# Murray.net
KiCad netlist of a schematic drawn in EAGLE
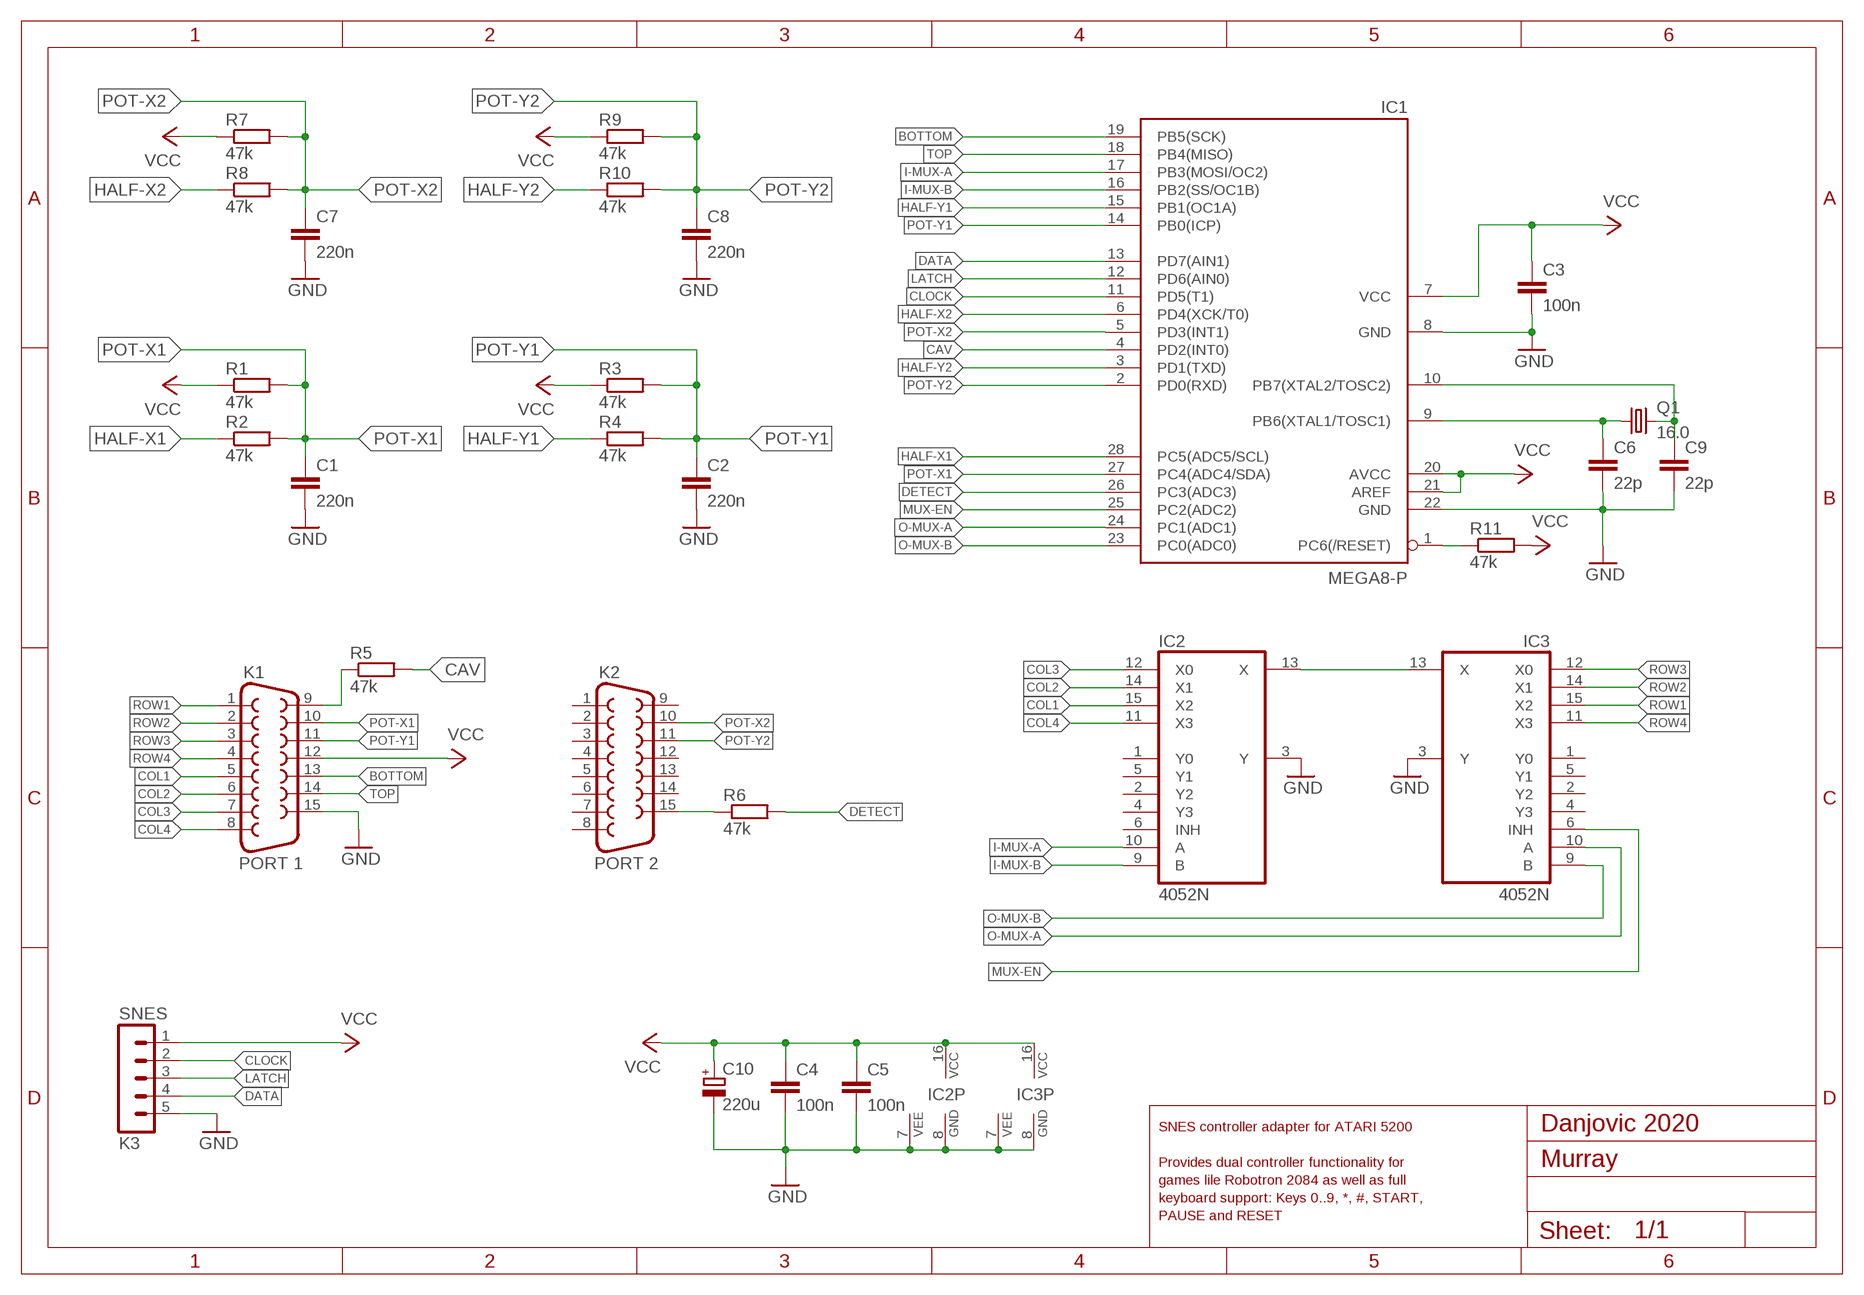
[diagram p0: schematic, sheet 1]

(export (version "E")
  (design (tool "Eeschema 10.0.6"))
  (components
    (comp (ref "C1")
      (value "220n")
      (footprint "eagle-import:C050-030X075")
      (libsource (lib "eagle-import") (part "C-EU050-030X075"))
    )
    (comp (ref "C2")
      (value "220n")
      (footprint "eagle-import:C050-030X075")
      (libsource (lib "eagle-import") (part "C-EU050-030X075"))
    )
    (comp (ref "C3")
      (value "100n")
      (footprint "eagle-import:C050-024X044")
      (libsource (lib "eagle-import") (part "C-EU050-024X044"))
    )
    (comp (ref "C4")
      (value "100n")
      (footprint "eagle-import:C050-024X044")
      (libsource (lib "eagle-import") (part "C-EU050-024X044"))
    )
    (comp (ref "C5")
      (value "100n")
      (footprint "eagle-import:C050-024X044")
      (libsource (lib "eagle-import") (part "C-EU050-024X044"))
    )
    (comp (ref "C6")
      (value "22p")
      (footprint "eagle-import:C025-024X044")
      (libsource (lib "eagle-import") (part "C-EU025-024X044"))
    )
    (comp (ref "C7")
      (value "220n")
      (footprint "eagle-import:C050-030X075")
      (libsource (lib "eagle-import") (part "C-EU050-030X075"))
    )
    (comp (ref "C8")
      (value "220n")
      (footprint "eagle-import:C050-030X075")
      (libsource (lib "eagle-import") (part "C-EU050-030X075"))
    )
    (comp (ref "C9")
      (value "22p")
      (footprint "eagle-import:C025-024X044")
      (libsource (lib "eagle-import") (part "C-EU025-024X044"))
    )
    (comp (ref "C10")
      (value "220u")
      (footprint "eagle-import:E2,5-6E")
      (libsource (lib "eagle-import") (part "CPOL-EUE2,5-6E"))
    )
    (comp (ref "IC1")
      (value "MEGA8-P")
      (footprint "eagle-import:DIL28-3")
      (libsource (lib "eagle-import") (part "MEGA8-P"))
    )
    (comp (ref "IC2")
      (value "4052N")
      (footprint "eagle-import:DIL16")
      (libsource (lib "eagle-import") (part "4052N"))
    )
    (comp (ref "IC3")
      (value "4052N")
      (footprint "eagle-import:DIL16")
      (libsource (lib "eagle-import") (part "4052N"))
    )
    (comp (ref "K1")
      (value "PORT 1")
      (footprint "eagle-import:F15H")
      (libsource (lib "eagle-import") (part "F15H"))
    )
    (comp (ref "K2")
      (value "PORT 2")
      (footprint "eagle-import:F15H")
      (libsource (lib "eagle-import") (part "F15H"))
    )
    (comp (ref "K3")
      (value "SNES")
      (footprint "eagle-import:MA05-1")
      (libsource (lib "eagle-import") (part "MA05-1"))
    )
    (comp (ref "Q1")
      (value "16.0")
      (footprint "eagle-import:TC26V")
      (libsource (lib "eagle-import") (part "CRYSTALTC26V"))
    )
    (comp (ref "R1")
      (value "47k")
      (footprint "eagle-import:0204_7")
      (libsource (lib "eagle-import") (part "R-EU_0204/7"))
    )
    (comp (ref "R2")
      (value "47k")
      (footprint "eagle-import:0204_7")
      (libsource (lib "eagle-import") (part "R-EU_0204/7"))
    )
    (comp (ref "R3")
      (value "47k")
      (footprint "eagle-import:0204_7")
      (libsource (lib "eagle-import") (part "R-EU_0204/7"))
    )
    (comp (ref "R4")
      (value "47k")
      (footprint "eagle-import:0204_7")
      (libsource (lib "eagle-import") (part "R-EU_0204/7"))
    )
    (comp (ref "R5")
      (value "47k")
      (footprint "eagle-import:0204_7")
      (libsource (lib "eagle-import") (part "R-EU_0204/7"))
    )
    (comp (ref "R6")
      (value "47k")
      (footprint "eagle-import:0204_7")
      (libsource (lib "eagle-import") (part "R-EU_0204/7"))
    )
    (comp (ref "R7")
      (value "47k")
      (footprint "eagle-import:0204_7")
      (libsource (lib "eagle-import") (part "R-EU_0204/7"))
    )
    (comp (ref "R8")
      (value "47k")
      (footprint "eagle-import:0204_7")
      (libsource (lib "eagle-import") (part "R-EU_0204/7"))
    )
    (comp (ref "R9")
      (value "47k")
      (footprint "eagle-import:0204_7")
      (libsource (lib "eagle-import") (part "R-EU_0204/7"))
    )
    (comp (ref "R10")
      (value "47k")
      (footprint "eagle-import:0204_7")
      (libsource (lib "eagle-import") (part "R-EU_0204/7"))
    )
    (comp (ref "R11")
      (value "47k")
      (footprint "eagle-import:0204_7")
      (libsource (lib "eagle-import") (part "R-EU_0204/7"))
    )
  )
  (nets
    (net (code "1") (name "BOTTOM") (class "Default")
      (node (ref "IC1") (pin "19") (pinfunction "PB5(SCK)_19") (pintype "bidirectional"))
      (node (ref "K1") (pin "13") (pinfunction "13_13") (pintype "passive"))
    )
    (net (code "2") (name "CAV") (class "Default")
      (node (ref "IC1") (pin "4") (pinfunction "PD2(INT0)_4") (pintype "bidirectional"))
      (node (ref "R5") (pin "2") (pinfunction "2_2") (pintype "passive"))
    )
    (net (code "3") (name "CLOCK") (class "Default")
      (node (ref "IC1") (pin "11") (pinfunction "PD5(T1)_11") (pintype "bidirectional"))
      (node (ref "K3") (pin "2") (pinfunction "2_2") (pintype "passive"))
    )
    (net (code "4") (name "COL1") (class "Default")
      (node (ref "IC2") (pin "15") (pinfunction "X2_15") (pintype "bidirectional"))
      (node (ref "K1") (pin "5") (pinfunction "5_5") (pintype "passive"))
    )
    (net (code "5") (name "COL2") (class "Default")
      (node (ref "IC2") (pin "14") (pinfunction "X1_14") (pintype "bidirectional"))
      (node (ref "K1") (pin "6") (pinfunction "6_6") (pintype "passive"))
    )
    (net (code "6") (name "COL3") (class "Default")
      (node (ref "IC2") (pin "12") (pinfunction "X0_12") (pintype "bidirectional"))
      (node (ref "K1") (pin "7") (pinfunction "7_7") (pintype "passive"))
    )
    (net (code "7") (name "COL4") (class "Default")
      (node (ref "IC2") (pin "11") (pinfunction "X3_11") (pintype "bidirectional"))
      (node (ref "K1") (pin "8") (pinfunction "8_8") (pintype "passive"))
    )
    (net (code "8") (name "DATA") (class "Default")
      (node (ref "IC1") (pin "13") (pinfunction "PD7(AIN1)_13") (pintype "bidirectional"))
      (node (ref "K3") (pin "4") (pinfunction "4_4") (pintype "passive"))
    )
    (net (code "9") (name "DETECT") (class "Default")
      (node (ref "IC1") (pin "26") (pinfunction "PC3(ADC3)_26") (pintype "bidirectional"))
      (node (ref "R6") (pin "2") (pinfunction "2_2") (pintype "passive"))
    )
    (net (code "10") (name "GND") (class "Default")
      (node (ref "C1") (pin "2") (pinfunction "2_2") (pintype "passive"))
      (node (ref "C10") (pin "-") (pinfunction "-_-") (pintype "passive"))
      (node (ref "C2") (pin "2") (pinfunction "2_2") (pintype "passive"))
      (node (ref "C3") (pin "2") (pinfunction "2_2") (pintype "passive"))
      (node (ref "C4") (pin "2") (pinfunction "2_2") (pintype "passive"))
      (node (ref "C5") (pin "2") (pinfunction "2_2") (pintype "passive"))
      (node (ref "C6") (pin "2") (pinfunction "2_2") (pintype "passive"))
      (node (ref "C7") (pin "2") (pinfunction "2_2") (pintype "passive"))
      (node (ref "C8") (pin "2") (pinfunction "2_2") (pintype "passive"))
      (node (ref "C9") (pin "2") (pinfunction "2_2") (pintype "passive"))
      (node (ref "IC1") (pin "22") (pinfunction "GND_22") (pintype "power_in"))
      (node (ref "IC1") (pin "8") (pinfunction "GND_8") (pintype "power_in"))
      (node (ref "IC2") (pin "3") (pinfunction "Y_3") (pintype "bidirectional"))
      (node (ref "IC2") (pin "7") (pinfunction "VEE_7") (pintype "power_in"))
      (node (ref "IC2") (pin "8") (pinfunction "GND_8") (pintype "power_in"))
      (node (ref "IC3") (pin "3") (pinfunction "Y_3") (pintype "bidirectional"))
      (node (ref "IC3") (pin "7") (pinfunction "VEE_7") (pintype "power_in"))
      (node (ref "IC3") (pin "8") (pinfunction "GND_8") (pintype "power_in"))
      (node (ref "K1") (pin "15") (pinfunction "15_15") (pintype "passive"))
      (node (ref "K3") (pin "5") (pinfunction "5_5") (pintype "passive"))
    )
    (net (code "11") (name "HALF-X1") (class "Default")
      (node (ref "IC1") (pin "28") (pinfunction "PC5(ADC5/SCL)_28") (pintype "bidirectional"))
      (node (ref "R2") (pin "1") (pinfunction "1_1") (pintype "passive"))
    )
    (net (code "12") (name "HALF-X2") (class "Default")
      (node (ref "IC1") (pin "6") (pinfunction "PD4(XCK/T0)_6") (pintype "bidirectional"))
      (node (ref "R8") (pin "1") (pinfunction "1_1") (pintype "passive"))
    )
    (net (code "13") (name "HALF-Y1") (class "Default")
      (node (ref "IC1") (pin "15") (pinfunction "PB1(OC1A)_15") (pintype "bidirectional"))
      (node (ref "R4") (pin "1") (pinfunction "1_1") (pintype "passive"))
    )
    (net (code "14") (name "HALF-Y2") (class "Default")
      (node (ref "IC1") (pin "3") (pinfunction "PD1(TXD)_3") (pintype "bidirectional"))
      (node (ref "R10") (pin "1") (pinfunction "1_1") (pintype "passive"))
    )
    (net (code "15") (name "I-MUX-A") (class "Default")
      (node (ref "IC1") (pin "17") (pinfunction "PB3(MOSI/OC2)_17") (pintype "bidirectional"))
      (node (ref "IC2") (pin "10") (pinfunction "A_10") (pintype "input"))
    )
    (net (code "16") (name "I-MUX-B") (class "Default")
      (node (ref "IC1") (pin "16") (pinfunction "PB2(SS/OC1B)_16") (pintype "bidirectional"))
      (node (ref "IC2") (pin "9") (pinfunction "B_9") (pintype "input"))
    )
    (net (code "17") (name "LATCH") (class "Default")
      (node (ref "IC1") (pin "12") (pinfunction "PD6(AIN0)_12") (pintype "bidirectional"))
      (node (ref "K3") (pin "3") (pinfunction "3_3") (pintype "passive"))
    )
    (net (code "18") (name "MUX-EN") (class "Default")
      (node (ref "IC1") (pin "25") (pinfunction "PC2(ADC2)_25") (pintype "bidirectional"))
      (node (ref "IC3") (pin "6") (pinfunction "INH_6") (pintype "input"))
    )
    (net (code "19") (name "Net-(IC1-PB6(XTAL1{slash}TOSC1))") (class "Default")
      (node (ref "C6") (pin "1") (pinfunction "1_1") (pintype "passive"))
      (node (ref "IC1") (pin "9") (pinfunction "PB6(XTAL1/TOSC1)_9") (pintype "bidirectional"))
      (node (ref "Q1") (pin "1") (pinfunction "1_1") (pintype "passive"))
    )
    (net (code "20") (name "Net-(IC1-PB7(XTAL2{slash}TOSC2))") (class "Default")
      (node (ref "C9") (pin "1") (pinfunction "1_1") (pintype "passive"))
      (node (ref "IC1") (pin "10") (pinfunction "PB7(XTAL2/TOSC2)_10") (pintype "bidirectional"))
      (node (ref "Q1") (pin "2") (pinfunction "2_2") (pintype "passive"))
    )
    (net (code "21") (name "Net-(IC1-PC6({slash}RESET))") (class "Default")
      (node (ref "IC1") (pin "1") (pinfunction "PC6(/RESET)_1") (pintype "bidirectional"))
      (node (ref "R11") (pin "1") (pinfunction "1_1") (pintype "passive"))
    )
    (net (code "22") (name "Net-(IC2A-X)") (class "Default")
      (node (ref "IC2") (pin "13") (pinfunction "X_13") (pintype "bidirectional"))
      (node (ref "IC3") (pin "13") (pinfunction "X_13") (pintype "bidirectional"))
    )
    (net (code "23") (name "Net-(K1-Pad9)") (class "Default")
      (node (ref "K1") (pin "9") (pinfunction "9_9") (pintype "passive"))
      (node (ref "R5") (pin "1") (pinfunction "1_1") (pintype "passive"))
    )
    (net (code "24") (name "Net-(K2-Pad15)") (class "Default")
      (node (ref "K2") (pin "15") (pinfunction "15_15") (pintype "passive"))
      (node (ref "R6") (pin "1") (pinfunction "1_1") (pintype "passive"))
    )
    (net (code "25") (name "O-MUX-A") (class "Default")
      (node (ref "IC1") (pin "24") (pinfunction "PC1(ADC1)_24") (pintype "bidirectional"))
      (node (ref "IC3") (pin "10") (pinfunction "A_10") (pintype "input"))
    )
    (net (code "26") (name "O-MUX-B") (class "Default")
      (node (ref "IC1") (pin "23") (pinfunction "PC0(ADC0)_23") (pintype "bidirectional"))
      (node (ref "IC3") (pin "9") (pinfunction "B_9") (pintype "input"))
    )
    (net (code "27") (name "POT-X1") (class "Default")
      (node (ref "C1") (pin "1") (pinfunction "1_1") (pintype "passive"))
      (node (ref "IC1") (pin "27") (pinfunction "PC4(ADC4/SDA)_27") (pintype "bidirectional"))
      (node (ref "K1") (pin "10") (pinfunction "10_10") (pintype "passive"))
      (node (ref "R1") (pin "2") (pinfunction "2_2") (pintype "passive"))
      (node (ref "R2") (pin "2") (pinfunction "2_2") (pintype "passive"))
    )
    (net (code "28") (name "POT-X2") (class "Default")
      (node (ref "C7") (pin "1") (pinfunction "1_1") (pintype "passive"))
      (node (ref "IC1") (pin "5") (pinfunction "PD3(INT1)_5") (pintype "bidirectional"))
      (node (ref "K2") (pin "10") (pinfunction "10_10") (pintype "passive"))
      (node (ref "R7") (pin "2") (pinfunction "2_2") (pintype "passive"))
      (node (ref "R8") (pin "2") (pinfunction "2_2") (pintype "passive"))
    )
    (net (code "29") (name "POT-Y1") (class "Default")
      (node (ref "C2") (pin "1") (pinfunction "1_1") (pintype "passive"))
      (node (ref "IC1") (pin "14") (pinfunction "PB0(ICP)_14") (pintype "bidirectional"))
      (node (ref "K1") (pin "11") (pinfunction "11_11") (pintype "passive"))
      (node (ref "R3") (pin "2") (pinfunction "2_2") (pintype "passive"))
      (node (ref "R4") (pin "2") (pinfunction "2_2") (pintype "passive"))
    )
    (net (code "30") (name "POT-Y2") (class "Default")
      (node (ref "C8") (pin "1") (pinfunction "1_1") (pintype "passive"))
      (node (ref "IC1") (pin "2") (pinfunction "PD0(RXD)_2") (pintype "bidirectional"))
      (node (ref "K2") (pin "11") (pinfunction "11_11") (pintype "passive"))
      (node (ref "R10") (pin "2") (pinfunction "2_2") (pintype "passive"))
      (node (ref "R9") (pin "2") (pinfunction "2_2") (pintype "passive"))
    )
    (net (code "31") (name "ROW1") (class "Default")
      (node (ref "IC3") (pin "15") (pinfunction "X2_15") (pintype "bidirectional"))
      (node (ref "K1") (pin "1") (pinfunction "1_1") (pintype "passive"))
    )
    (net (code "32") (name "ROW2") (class "Default")
      (node (ref "IC3") (pin "14") (pinfunction "X1_14") (pintype "bidirectional"))
      (node (ref "K1") (pin "2") (pinfunction "2_2") (pintype "passive"))
    )
    (net (code "33") (name "ROW3") (class "Default")
      (node (ref "IC3") (pin "12") (pinfunction "X0_12") (pintype "bidirectional"))
      (node (ref "K1") (pin "3") (pinfunction "3_3") (pintype "passive"))
    )
    (net (code "34") (name "ROW4") (class "Default")
      (node (ref "IC3") (pin "11") (pinfunction "X3_11") (pintype "bidirectional"))
      (node (ref "K1") (pin "4") (pinfunction "4_4") (pintype "passive"))
    )
    (net (code "35") (name "TOP") (class "Default")
      (node (ref "IC1") (pin "18") (pinfunction "PB4(MISO)_18") (pintype "bidirectional"))
      (node (ref "K1") (pin "14") (pinfunction "14_14") (pintype "passive"))
    )
    (net (code "36") (name "VCC") (class "Default")
      (node (ref "C10") (pin "+") (pinfunction "+_+") (pintype "passive"))
      (node (ref "C3") (pin "1") (pinfunction "1_1") (pintype "passive"))
      (node (ref "C4") (pin "1") (pinfunction "1_1") (pintype "passive"))
      (node (ref "C5") (pin "1") (pinfunction "1_1") (pintype "passive"))
      (node (ref "IC1") (pin "20") (pinfunction "AVCC_20") (pintype "power_in"))
      (node (ref "IC1") (pin "21") (pinfunction "AREF_21") (pintype "passive"))
      (node (ref "IC1") (pin "7") (pinfunction "VCC_7") (pintype "power_in"))
      (node (ref "IC2") (pin "16") (pinfunction "VCC_16") (pintype "power_in"))
      (node (ref "IC3") (pin "16") (pinfunction "VCC_16") (pintype "power_in"))
      (node (ref "K1") (pin "12") (pinfunction "12_12") (pintype "passive"))
      (node (ref "K3") (pin "1") (pinfunction "1_1") (pintype "passive"))
      (node (ref "R1") (pin "1") (pinfunction "1_1") (pintype "passive"))
      (node (ref "R11") (pin "2") (pinfunction "2_2") (pintype "passive"))
      (node (ref "R3") (pin "1") (pinfunction "1_1") (pintype "passive"))
      (node (ref "R7") (pin "1") (pinfunction "1_1") (pintype "passive"))
      (node (ref "R9") (pin "1") (pinfunction "1_1") (pintype "passive"))
    )
    (net (code "37") (name "unconnected-(IC2A-INH-Pad6)") (class "Default")
      (node (ref "IC2") (pin "6") (pinfunction "INH_6") (pintype "input"))
    )
    (net (code "38") (name "unconnected-(IC2A-Y0-Pad1)") (class "Default")
      (node (ref "IC2") (pin "1") (pinfunction "Y0_1") (pintype "bidirectional"))
    )
    (net (code "39") (name "unconnected-(IC2A-Y1-Pad5)") (class "Default")
      (node (ref "IC2") (pin "5") (pinfunction "Y1_5") (pintype "bidirectional"))
    )
    (net (code "40") (name "unconnected-(IC2A-Y2-Pad2)") (class "Default")
      (node (ref "IC2") (pin "2") (pinfunction "Y2_2") (pintype "bidirectional"))
    )
    (net (code "41") (name "unconnected-(IC2A-Y3-Pad4)") (class "Default")
      (node (ref "IC2") (pin "4") (pinfunction "Y3_4") (pintype "bidirectional"))
    )
    (net (code "42") (name "unconnected-(IC3A-Y0-Pad1)") (class "Default")
      (node (ref "IC3") (pin "1") (pinfunction "Y0_1") (pintype "bidirectional"))
    )
    (net (code "43") (name "unconnected-(IC3A-Y1-Pad5)") (class "Default")
      (node (ref "IC3") (pin "5") (pinfunction "Y1_5") (pintype "bidirectional"))
    )
    (net (code "44") (name "unconnected-(IC3A-Y2-Pad2)") (class "Default")
      (node (ref "IC3") (pin "2") (pinfunction "Y2_2") (pintype "bidirectional"))
    )
    (net (code "45") (name "unconnected-(IC3A-Y3-Pad4)") (class "Default")
      (node (ref "IC3") (pin "4") (pinfunction "Y3_4") (pintype "bidirectional"))
    )
    (net (code "46") (name "unconnected-(K2-Pad1)") (class "Default")
      (node (ref "K2") (pin "1") (pinfunction "1_1") (pintype "passive"))
    )
    (net (code "47") (name "unconnected-(K2-Pad2)") (class "Default")
      (node (ref "K2") (pin "2") (pinfunction "2_2") (pintype "passive"))
    )
    (net (code "48") (name "unconnected-(K2-Pad3)") (class "Default")
      (node (ref "K2") (pin "3") (pinfunction "3_3") (pintype "passive"))
    )
    (net (code "49") (name "unconnected-(K2-Pad4)") (class "Default")
      (node (ref "K2") (pin "4") (pinfunction "4_4") (pintype "passive"))
    )
    (net (code "50") (name "unconnected-(K2-Pad5)") (class "Default")
      (node (ref "K2") (pin "5") (pinfunction "5_5") (pintype "passive"))
    )
    (net (code "51") (name "unconnected-(K2-Pad6)") (class "Default")
      (node (ref "K2") (pin "6") (pinfunction "6_6") (pintype "passive"))
    )
    (net (code "52") (name "unconnected-(K2-Pad7)") (class "Default")
      (node (ref "K2") (pin "7") (pinfunction "7_7") (pintype "passive"))
    )
    (net (code "53") (name "unconnected-(K2-Pad8)") (class "Default")
      (node (ref "K2") (pin "8") (pinfunction "8_8") (pintype "passive"))
    )
    (net (code "54") (name "unconnected-(K2-Pad9)") (class "Default")
      (node (ref "K2") (pin "9") (pinfunction "9_9") (pintype "passive"))
    )
    (net (code "55") (name "unconnected-(K2-Pad12)") (class "Default")
      (node (ref "K2") (pin "12") (pinfunction "12_12") (pintype "passive"))
    )
    (net (code "56") (name "unconnected-(K2-Pad13)") (class "Default")
      (node (ref "K2") (pin "13") (pinfunction "13_13") (pintype "passive"))
    )
    (net (code "57") (name "unconnected-(K2-Pad14)") (class "Default")
      (node (ref "K2") (pin "14") (pinfunction "14_14") (pintype "passive"))
    )
  )
)
